# TICC3000WiFiBreakout.net
KiCad netlist of a schematic drawn in EAGLE
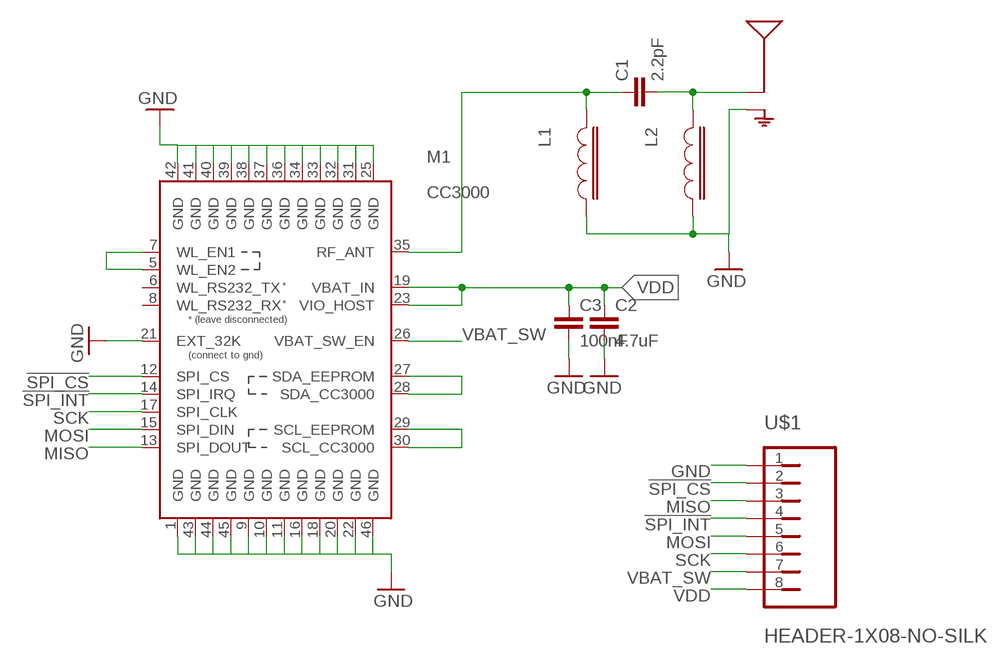
[diagram p0: schematic, sheet 1]

(export (version "E")
  (design (tool "Eeschema 10.0.6"))
  (components
    (comp (ref "ANT1")
      (value "ANTENNA-TRACE-WITH-GND-2.450GHZ-TI-AN043")
      (footprint "eagle-import:ANTENNA-2.450GHZ-TI-AN043")
      (libsource (lib "eagle-import") (part "ANTENNA-TRACE-WITH-GND-2.450GHZ-TI-AN043"))
    )
    (comp (ref "C1")
      (value "2.2pF")
      (footprint "eagle-import:0805")
      (libsource (lib "eagle-import") (part "CAP-0805"))
    )
    (comp (ref "C2")
      (value "4.7uF")
      (footprint "eagle-import:0805")
      (libsource (lib "eagle-import") (part "CAP-0805"))
    )
    (comp (ref "C3")
      (value "100nF")
      (footprint "eagle-import:0805")
      (libsource (lib "eagle-import") (part "CAP-0805"))
    )
    (comp (ref "L1")
      (value "INDUCTOR-0402-MIN")
      (footprint "eagle-import:0402-MIN")
      (libsource (lib "eagle-import") (part "INDUCTOR-0402-MIN"))
    )
    (comp (ref "L2")
      (value "INDUCTOR-0402-MIN")
      (footprint "eagle-import:0402-MIN")
      (libsource (lib "eagle-import") (part "INDUCTOR-0402-MIN"))
    )
    (comp (ref "M1")
      (value "CC3000")
      (footprint "eagle-import:TI-CC3000-WIFI-MODULE")
      (libsource (lib "eagle-import") (part "TI-CC3000-WIFI-MODULE"))
    )
    (comp (ref "U$1")
      (value "HEADER-1X08-NO-SILK")
      (footprint "eagle-import:HEADER-1X08-NO-SILK")
      (libsource (lib "eagle-import") (part "HEADER-1X08-NO-SILK"))
    )
  )
  (nets
    (net (code "1") (name "/MISO") (class "Default")
      (node (ref "M1") (pin "13") (pinfunction "SPI_DOUT_13") (pintype "bidirectional"))
      (node (ref "U$1") (pin "3") (pinfunction "3_3") (pintype "bidirectional"))
    )
    (net (code "2") (name "/MOSI") (class "Default")
      (node (ref "M1") (pin "15") (pinfunction "SPI_DIN_15") (pintype "bidirectional"))
      (node (ref "U$1") (pin "5") (pinfunction "5_5") (pintype "bidirectional"))
    )
    (net (code "3") (name "/SCK") (class "Default")
      (node (ref "M1") (pin "17") (pinfunction "SPI_CLK_17") (pintype "bidirectional"))
      (node (ref "U$1") (pin "6") (pinfunction "6_6") (pintype "bidirectional"))
    )
    (net (code "4") (name "/VBAT_SW") (class "Default")
      (node (ref "M1") (pin "26") (pinfunction "VBAT_SW_EN_26") (pintype "bidirectional"))
      (node (ref "U$1") (pin "7") (pinfunction "7_7") (pintype "bidirectional"))
    )
    (net (code "5") (name "/~{SPI_CS}") (class "Default")
      (node (ref "M1") (pin "12") (pinfunction "SPI_CS_12") (pintype "bidirectional"))
      (node (ref "U$1") (pin "2") (pinfunction "2_2") (pintype "bidirectional"))
    )
    (net (code "6") (name "/~{SPI_INT}") (class "Default")
      (node (ref "M1") (pin "14") (pinfunction "SPI_IRQ_14") (pintype "bidirectional"))
      (node (ref "U$1") (pin "4") (pinfunction "4_4") (pintype "bidirectional"))
    )
    (net (code "7") (name "GND") (class "Default")
      (node (ref "ANT1") (pin "RFGND") (pinfunction "GND_RFGND") (pintype "power_in"))
      (node (ref "C2") (pin "1") (pinfunction "1_1") (pintype "bidirectional"))
      (node (ref "C3") (pin "1") (pinfunction "1_1") (pintype "bidirectional"))
      (node (ref "L1") (pin "2") (pinfunction "2_2") (pintype "bidirectional"))
      (node (ref "L2") (pin "2") (pinfunction "2_2") (pintype "bidirectional"))
      (node (ref "M1") (pin "1") (pinfunction "GND_1") (pintype "bidirectional"))
      (node (ref "M1") (pin "10") (pinfunction "GND_10") (pintype "bidirectional"))
      (node (ref "M1") (pin "11") (pinfunction "GND_11") (pintype "bidirectional"))
      (node (ref "M1") (pin "16") (pinfunction "GND_16") (pintype "bidirectional"))
      (node (ref "M1") (pin "18") (pinfunction "GND_18") (pintype "bidirectional"))
      (node (ref "M1") (pin "20") (pinfunction "GND_20") (pintype "bidirectional"))
      (node (ref "M1") (pin "21") (pinfunction "EXT_32K_21") (pintype "bidirectional"))
      (node (ref "M1") (pin "22") (pinfunction "GND_22") (pintype "bidirectional"))
      (node (ref "M1") (pin "25") (pinfunction "GND_25") (pintype "bidirectional"))
      (node (ref "M1") (pin "31") (pinfunction "GND_31") (pintype "bidirectional"))
      (node (ref "M1") (pin "32") (pinfunction "GND_32") (pintype "bidirectional"))
      (node (ref "M1") (pin "33") (pinfunction "GND_33") (pintype "bidirectional"))
      (node (ref "M1") (pin "34") (pinfunction "GND_34") (pintype "bidirectional"))
      (node (ref "M1") (pin "36") (pinfunction "GND_36") (pintype "bidirectional"))
      (node (ref "M1") (pin "37") (pinfunction "GND_37") (pintype "bidirectional"))
      (node (ref "M1") (pin "38") (pinfunction "GND_38") (pintype "bidirectional"))
      (node (ref "M1") (pin "39") (pinfunction "GND_39") (pintype "bidirectional"))
      (node (ref "M1") (pin "40") (pinfunction "GND_40") (pintype "bidirectional"))
      (node (ref "M1") (pin "41") (pinfunction "GND_41") (pintype "bidirectional"))
      (node (ref "M1") (pin "42") (pinfunction "GND_42") (pintype "bidirectional"))
      (node (ref "M1") (pin "43") (pinfunction "GND_43") (pintype "bidirectional"))
      (node (ref "M1") (pin "44") (pinfunction "GND_44") (pintype "bidirectional"))
      (node (ref "M1") (pin "45") (pinfunction "GND_45") (pintype "bidirectional"))
      (node (ref "M1") (pin "46") (pinfunction "GND_46") (pintype "bidirectional"))
      (node (ref "M1") (pin "9") (pinfunction "GND_9") (pintype "bidirectional"))
      (node (ref "U$1") (pin "1") (pinfunction "1_1") (pintype "bidirectional"))
    )
    (net (code "8") (name "Net-(ANT1-RF)") (class "Default")
      (node (ref "ANT1") (pin "ANT") (pinfunction "RF_ANT") (pintype "bidirectional"))
      (node (ref "C1") (pin "1") (pinfunction "1_1") (pintype "bidirectional"))
      (node (ref "L2") (pin "1") (pinfunction "1_1") (pintype "bidirectional"))
    )
    (net (code "9") (name "Net-(M1-RF_ANT)") (class "Default")
      (node (ref "C1") (pin "2") (pinfunction "2_2") (pintype "bidirectional"))
      (node (ref "L1") (pin "1") (pinfunction "1_1") (pintype "bidirectional"))
      (node (ref "M1") (pin "35") (pinfunction "RF_ANT_35") (pintype "bidirectional"))
    )
    (net (code "10") (name "Net-(M1-SCL_CC3000)") (class "Default")
      (node (ref "M1") (pin "29") (pinfunction "SCL_EEPROM_29") (pintype "bidirectional"))
      (node (ref "M1") (pin "30") (pinfunction "SCL_CC3000_30") (pintype "bidirectional"))
    )
    (net (code "11") (name "Net-(M1-SDA_CC3000)") (class "Default")
      (node (ref "M1") (pin "27") (pinfunction "SDA_EEPROM_27") (pintype "bidirectional"))
      (node (ref "M1") (pin "28") (pinfunction "SDA_CC3000_28") (pintype "bidirectional"))
    )
    (net (code "12") (name "Net-(M1-WL_EN1)") (class "Default")
      (node (ref "M1") (pin "5") (pinfunction "WL_EN2_5") (pintype "bidirectional"))
      (node (ref "M1") (pin "7") (pinfunction "WL_EN1_7") (pintype "bidirectional"))
    )
    (net (code "13") (name "VDD") (class "Default")
      (node (ref "C2") (pin "2") (pinfunction "2_2") (pintype "bidirectional"))
      (node (ref "C3") (pin "2") (pinfunction "2_2") (pintype "bidirectional"))
      (node (ref "M1") (pin "19") (pinfunction "VBAT_IN_19") (pintype "bidirectional"))
      (node (ref "M1") (pin "23") (pinfunction "VIO_HOST_23") (pintype "bidirectional"))
      (node (ref "U$1") (pin "8") (pinfunction "8_8") (pintype "bidirectional"))
    )
    (net (code "14") (name "unconnected-(M1-WL_RS232_RX-Pad8)") (class "Default")
      (node (ref "M1") (pin "8") (pinfunction "WL_RS232_RX_8") (pintype "bidirectional"))
    )
    (net (code "15") (name "unconnected-(M1-WL_RS232_TX-Pad6)") (class "Default")
      (node (ref "M1") (pin "6") (pinfunction "WL_RS232_TX_6") (pintype "bidirectional"))
    )
  )
)
